# indicator-4x3-chain-v2.net
KiCad netlist of a schematic drawn in EAGLE
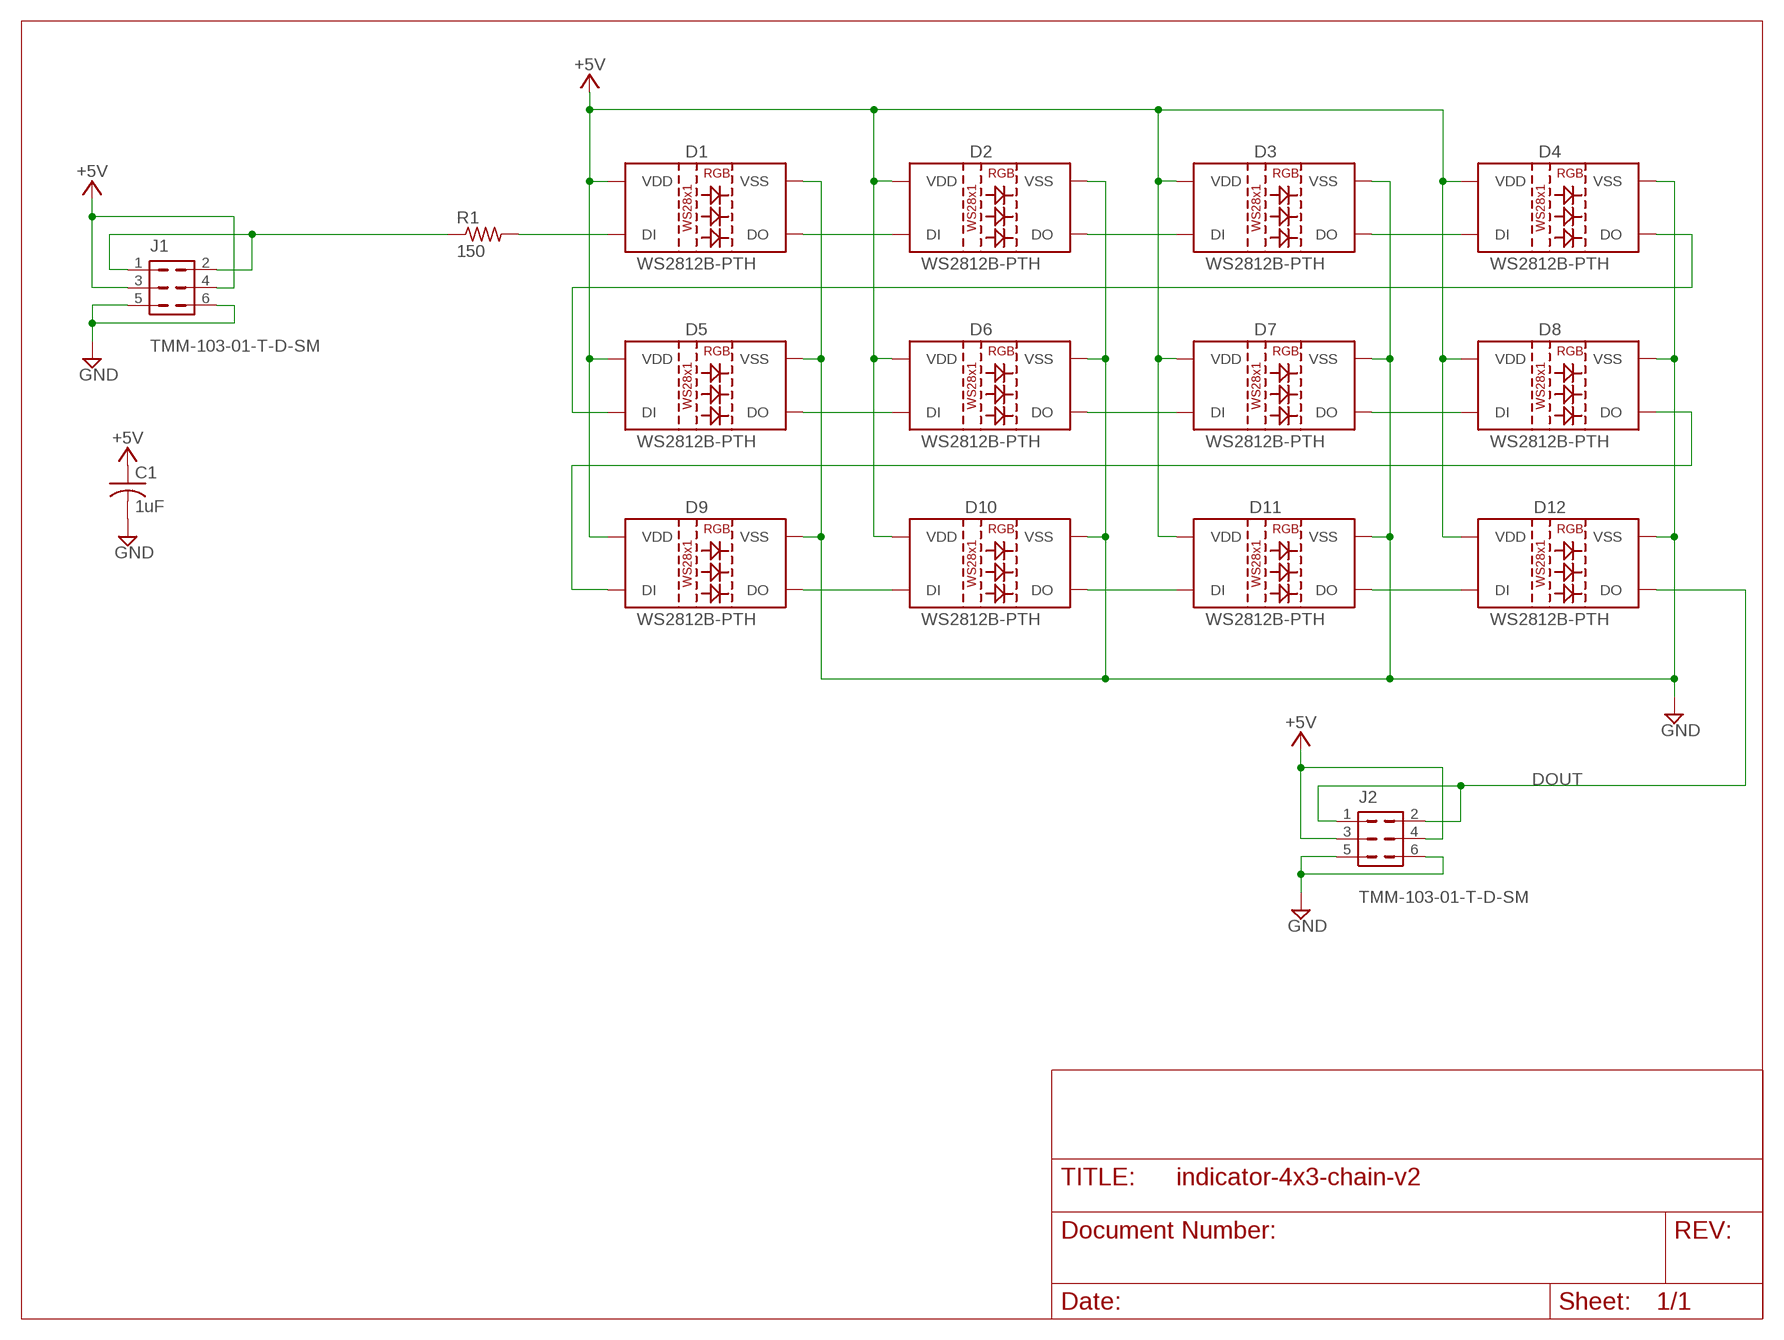
[diagram p0: schematic, sheet 1]

(export (version "E")
  (design (tool "Eeschema 10.0.6"))
  (components
    (comp (ref "C1")
      (value "1uF")
      (footprint "eagle-import:C0603K")
      (libsource (lib "eagle-import") (part "C-USC0603K"))
    )
    (comp (ref "D1")
      (value "WS2812B-PTH")
      (footprint "eagle-import:WS2812B-PTH-KIT")
      (libsource (lib "eagle-import") (part "WS2812B-PTH"))
    )
    (comp (ref "D2")
      (value "WS2812B-PTH")
      (footprint "eagle-import:WS2812B-PTH-KIT")
      (libsource (lib "eagle-import") (part "WS2812B-PTH"))
    )
    (comp (ref "D3")
      (value "WS2812B-PTH")
      (footprint "eagle-import:WS2812B-PTH-KIT")
      (libsource (lib "eagle-import") (part "WS2812B-PTH"))
    )
    (comp (ref "D4")
      (value "WS2812B-PTH")
      (footprint "eagle-import:WS2812B-PTH-KIT")
      (libsource (lib "eagle-import") (part "WS2812B-PTH"))
    )
    (comp (ref "D5")
      (value "WS2812B-PTH")
      (footprint "eagle-import:WS2812B-PTH-KIT")
      (libsource (lib "eagle-import") (part "WS2812B-PTH"))
    )
    (comp (ref "D6")
      (value "WS2812B-PTH")
      (footprint "eagle-import:WS2812B-PTH-KIT")
      (libsource (lib "eagle-import") (part "WS2812B-PTH"))
    )
    (comp (ref "D7")
      (value "WS2812B-PTH")
      (footprint "eagle-import:WS2812B-PTH-KIT")
      (libsource (lib "eagle-import") (part "WS2812B-PTH"))
    )
    (comp (ref "D8")
      (value "WS2812B-PTH")
      (footprint "eagle-import:WS2812B-PTH-KIT")
      (libsource (lib "eagle-import") (part "WS2812B-PTH"))
    )
    (comp (ref "D9")
      (value "WS2812B-PTH")
      (footprint "eagle-import:WS2812B-PTH-KIT")
      (libsource (lib "eagle-import") (part "WS2812B-PTH"))
    )
    (comp (ref "D10")
      (value "WS2812B-PTH")
      (footprint "eagle-import:WS2812B-PTH-KIT")
      (libsource (lib "eagle-import") (part "WS2812B-PTH"))
    )
    (comp (ref "D11")
      (value "WS2812B-PTH")
      (footprint "eagle-import:WS2812B-PTH-KIT")
      (libsource (lib "eagle-import") (part "WS2812B-PTH"))
    )
    (comp (ref "D12")
      (value "WS2812B-PTH")
      (footprint "eagle-import:WS2812B-PTH-KIT")
      (libsource (lib "eagle-import") (part "WS2812B-PTH"))
    )
    (comp (ref "J1")
      (value "TMM-103-01-T-D-SM")
      (footprint "eagle-import:2MM-SMD-HEADER-2X3")
      (libsource (lib "eagle-import") (part "TMM-103-01-T-D-SM"))
    )
    (comp (ref "J2")
      (value "TMM-103-01-T-D-SM")
      (footprint "eagle-import:2MM-SMD-HEADER-2X3")
      (libsource (lib "eagle-import") (part "TMM-103-01-T-D-SM"))
    )
    (comp (ref "R1")
      (value "150")
      (footprint "eagle-import:R0603")
      (libsource (lib "eagle-import") (part "R-US_R0603"))
    )
  )
  (nets
    (net (code "1") (name "+5V") (class "Default")
      (node (ref "C1") (pin "1") (pinfunction "1_1") (pintype "passive"))
      (node (ref "D1") (pin "2") (pinfunction "VDD_2") (pintype "bidirectional"))
      (node (ref "D10") (pin "2") (pinfunction "VDD_2") (pintype "bidirectional"))
      (node (ref "D11") (pin "2") (pinfunction "VDD_2") (pintype "bidirectional"))
      (node (ref "D12") (pin "2") (pinfunction "VDD_2") (pintype "bidirectional"))
      (node (ref "D2") (pin "2") (pinfunction "VDD_2") (pintype "bidirectional"))
      (node (ref "D3") (pin "2") (pinfunction "VDD_2") (pintype "bidirectional"))
      (node (ref "D4") (pin "2") (pinfunction "VDD_2") (pintype "bidirectional"))
      (node (ref "D5") (pin "2") (pinfunction "VDD_2") (pintype "bidirectional"))
      (node (ref "D6") (pin "2") (pinfunction "VDD_2") (pintype "bidirectional"))
      (node (ref "D7") (pin "2") (pinfunction "VDD_2") (pintype "bidirectional"))
      (node (ref "D8") (pin "2") (pinfunction "VDD_2") (pintype "bidirectional"))
      (node (ref "D9") (pin "2") (pinfunction "VDD_2") (pintype "bidirectional"))
      (node (ref "J1") (pin "3") (pinfunction "3_3") (pintype "passive"))
      (node (ref "J1") (pin "4") (pinfunction "4_4") (pintype "passive"))
      (node (ref "J2") (pin "3") (pinfunction "3_3") (pintype "passive"))
      (node (ref "J2") (pin "4") (pinfunction "4_4") (pintype "passive"))
    )
    (net (code "2") (name "/DOUT") (class "Default")
      (node (ref "D12") (pin "4") (pinfunction "DO_4") (pintype "bidirectional"))
      (node (ref "J2") (pin "1") (pinfunction "1_1") (pintype "passive"))
      (node (ref "J2") (pin "2") (pinfunction "2_2") (pintype "passive"))
    )
    (net (code "3") (name "GND") (class "Default")
      (node (ref "C1") (pin "2") (pinfunction "2_2") (pintype "passive"))
      (node (ref "D1") (pin "3") (pinfunction "VSS_3") (pintype "bidirectional"))
      (node (ref "D10") (pin "3") (pinfunction "VSS_3") (pintype "bidirectional"))
      (node (ref "D11") (pin "3") (pinfunction "VSS_3") (pintype "bidirectional"))
      (node (ref "D12") (pin "3") (pinfunction "VSS_3") (pintype "bidirectional"))
      (node (ref "D2") (pin "3") (pinfunction "VSS_3") (pintype "bidirectional"))
      (node (ref "D3") (pin "3") (pinfunction "VSS_3") (pintype "bidirectional"))
      (node (ref "D4") (pin "3") (pinfunction "VSS_3") (pintype "bidirectional"))
      (node (ref "D5") (pin "3") (pinfunction "VSS_3") (pintype "bidirectional"))
      (node (ref "D6") (pin "3") (pinfunction "VSS_3") (pintype "bidirectional"))
      (node (ref "D7") (pin "3") (pinfunction "VSS_3") (pintype "bidirectional"))
      (node (ref "D8") (pin "3") (pinfunction "VSS_3") (pintype "bidirectional"))
      (node (ref "D9") (pin "3") (pinfunction "VSS_3") (pintype "bidirectional"))
      (node (ref "J1") (pin "5") (pinfunction "5_5") (pintype "passive"))
      (node (ref "J1") (pin "6") (pinfunction "6_6") (pintype "passive"))
      (node (ref "J2") (pin "5") (pinfunction "5_5") (pintype "passive"))
      (node (ref "J2") (pin "6") (pinfunction "6_6") (pintype "passive"))
    )
    (net (code "4") (name "Net-(D1-DI)") (class "Default")
      (node (ref "D1") (pin "1") (pinfunction "DI_1") (pintype "bidirectional"))
      (node (ref "R1") (pin "2") (pinfunction "2_2") (pintype "passive"))
    )
    (net (code "5") (name "Net-(D1-DO)") (class "Default")
      (node (ref "D1") (pin "4") (pinfunction "DO_4") (pintype "bidirectional"))
      (node (ref "D2") (pin "1") (pinfunction "DI_1") (pintype "bidirectional"))
    )
    (net (code "6") (name "Net-(D2-DO)") (class "Default")
      (node (ref "D2") (pin "4") (pinfunction "DO_4") (pintype "bidirectional"))
      (node (ref "D3") (pin "1") (pinfunction "DI_1") (pintype "bidirectional"))
    )
    (net (code "7") (name "Net-(D3-DO)") (class "Default")
      (node (ref "D3") (pin "4") (pinfunction "DO_4") (pintype "bidirectional"))
      (node (ref "D4") (pin "1") (pinfunction "DI_1") (pintype "bidirectional"))
    )
    (net (code "8") (name "Net-(D4-DO)") (class "Default")
      (node (ref "D4") (pin "4") (pinfunction "DO_4") (pintype "bidirectional"))
      (node (ref "D5") (pin "1") (pinfunction "DI_1") (pintype "bidirectional"))
    )
    (net (code "9") (name "Net-(D5-DO)") (class "Default")
      (node (ref "D5") (pin "4") (pinfunction "DO_4") (pintype "bidirectional"))
      (node (ref "D6") (pin "1") (pinfunction "DI_1") (pintype "bidirectional"))
    )
    (net (code "10") (name "Net-(D6-DO)") (class "Default")
      (node (ref "D6") (pin "4") (pinfunction "DO_4") (pintype "bidirectional"))
      (node (ref "D7") (pin "1") (pinfunction "DI_1") (pintype "bidirectional"))
    )
    (net (code "11") (name "Net-(D7-DO)") (class "Default")
      (node (ref "D7") (pin "4") (pinfunction "DO_4") (pintype "bidirectional"))
      (node (ref "D8") (pin "1") (pinfunction "DI_1") (pintype "bidirectional"))
    )
    (net (code "12") (name "Net-(D8-DO)") (class "Default")
      (node (ref "D8") (pin "4") (pinfunction "DO_4") (pintype "bidirectional"))
      (node (ref "D9") (pin "1") (pinfunction "DI_1") (pintype "bidirectional"))
    )
    (net (code "13") (name "Net-(D10-DI)") (class "Default")
      (node (ref "D10") (pin "1") (pinfunction "DI_1") (pintype "bidirectional"))
      (node (ref "D9") (pin "4") (pinfunction "DO_4") (pintype "bidirectional"))
    )
    (net (code "14") (name "Net-(D10-DO)") (class "Default")
      (node (ref "D10") (pin "4") (pinfunction "DO_4") (pintype "bidirectional"))
      (node (ref "D11") (pin "1") (pinfunction "DI_1") (pintype "bidirectional"))
    )
    (net (code "15") (name "Net-(D11-DO)") (class "Default")
      (node (ref "D11") (pin "4") (pinfunction "DO_4") (pintype "bidirectional"))
      (node (ref "D12") (pin "1") (pinfunction "DI_1") (pintype "bidirectional"))
    )
    (net (code "16") (name "Net-(J1-Pad1)") (class "Default")
      (node (ref "J1") (pin "1") (pinfunction "1_1") (pintype "passive"))
      (node (ref "J1") (pin "2") (pinfunction "2_2") (pintype "passive"))
      (node (ref "R1") (pin "1") (pinfunction "1_1") (pintype "passive"))
    )
  )
)
